# X7A15T-Decoupling.net
KiCad netlist of a schematic drawn in Altium Designer
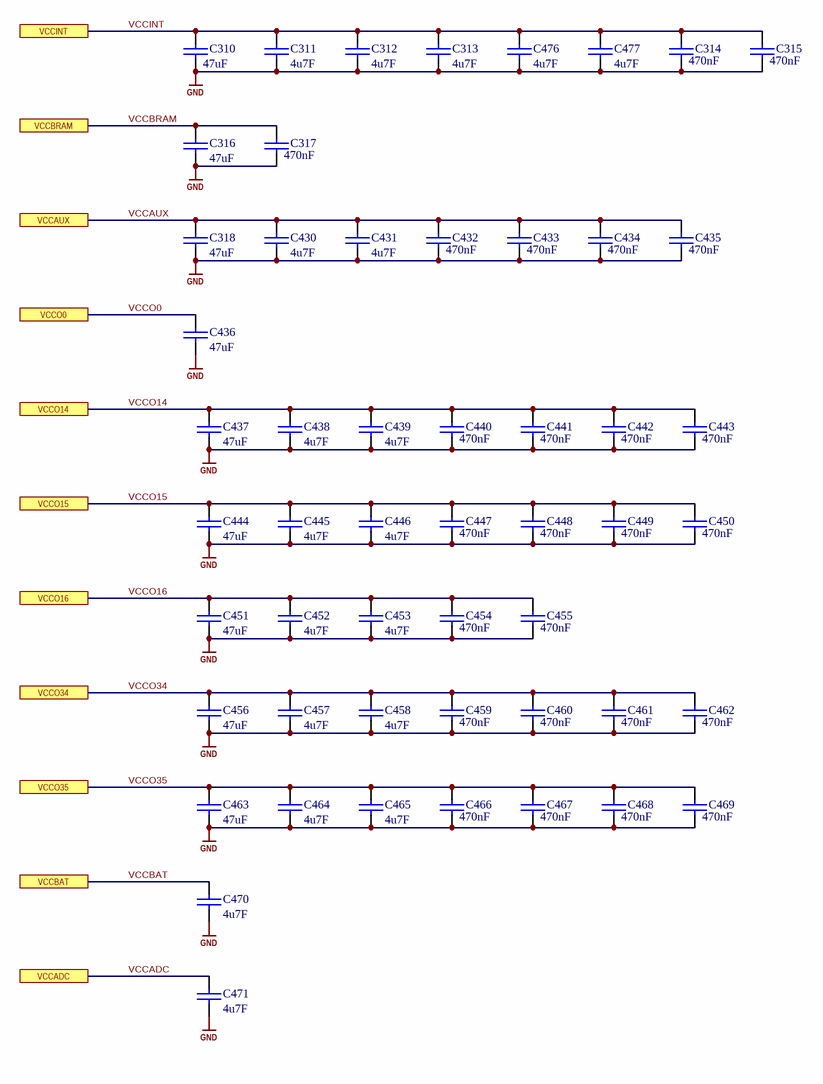
[diagram p0: X7A15T-Decoupling.SchDoc]

(export (version "E")
  (design (tool "Eeschema 10.0.6"))
  (components
    (comp (ref "C310")
      (value "47uF")
      (footprint "C1206 Reflow")
      (description "CAP CER 47UF 10V X5R 1206")
      (fields (field (name "MFR") "MURATA") (field (name "02. DISTRIBUTOR PART NUMBER") "1276-3063-6-ND"))
      (libsource (lib "SCT8-Board1") (part "CAP"))
    )
    (comp (ref "C311")
      (value "4u7F")
      (footprint "C0402 RevOne")
      (description "CAP CER 4.7UF 6.3V X5R 0402")
      (fields
        (field (name "02. DISTRIBUTOR PART NUMBER") "1276-1481-6-ND")
        (field (name "07. MANUFACTURER  PART NUMBER") "CL05A475KQ5NRNC")
      )
      (libsource (lib "SCT8-Board1") (part "CAP"))
    )
    (comp (ref "C312")
      (value "4u7F")
      (footprint "C0402 RevOne")
      (description "CAP CER 4.7UF 6.3V X5R 0402")
      (fields
        (field (name "02. DISTRIBUTOR PART NUMBER") "1276-1481-6-ND")
        (field (name "07. MANUFACTURER  PART NUMBER") "CL05A475KQ5NRNC")
      )
      (libsource (lib "SCT8-Board1") (part "CAP"))
    )
    (comp (ref "C313")
      (value "4u7F")
      (footprint "C0402 RevOne")
      (description "CAP CER 4.7UF 6.3V X5R 0402")
      (fields
        (field (name "02. DISTRIBUTOR PART NUMBER") "1276-1481-6-ND")
        (field (name "07. MANUFACTURER  PART NUMBER") "CL05A475KQ5NRNC")
      )
      (libsource (lib "SCT8-Board1") (part "CAP"))
    )
    (comp (ref "C314")
      (value "470nF")
      (footprint "C0402 RevOne")
      (description "CAP CER 0.47UF 10V X5R 0402")
      (fields
        (field (name "02. DISTRIBUTOR PART NUMBER") "1276-1173-6-ND")
        (field (name "07. MANUFACTURER  PART NUMBER") "CL05A474KP5NNNC")
      )
      (libsource (lib "SCT8-Board1") (part "CAP"))
    )
    (comp (ref "C315")
      (value "470nF")
      (footprint "C0402 RevOne")
      (description "CAP CER 0.47UF 10V X5R 0402")
      (fields
        (field (name "02. DISTRIBUTOR PART NUMBER") "1276-1173-6-ND")
        (field (name "07. MANUFACTURER  PART NUMBER") "CL05A474KP5NNNC")
      )
      (libsource (lib "SCT8-Board1") (part "CAP"))
    )
    (comp (ref "C316")
      (value "47uF")
      (footprint "C0805 Reflow")
      (description "CAP CER 47UF 10V X5R 0805")
      (fields (field (name "MFR") "MURATA") (field (name "02. DISTRIBUTOR PART NUMBER") "490-9961-6-ND"))
      (libsource (lib "SCT8-Board1") (part "CAP"))
    )
    (comp (ref "C317")
      (value "470nF")
      (footprint "C0402 RevOne")
      (description "CAP CER 0.47UF 10V X5R 0402")
      (fields
        (field (name "02. DISTRIBUTOR PART NUMBER") "1276-1173-6-ND")
        (field (name "07. MANUFACTURER  PART NUMBER") "CL05A474KP5NNNC")
      )
      (libsource (lib "SCT8-Board1") (part "CAP"))
    )
    (comp (ref "C318")
      (value "47uF")
      (footprint "C0805 Reflow")
      (description "CAP CER 47UF 10V X5R 0805")
      (fields (field (name "MFR") "MURATA") (field (name "02. DISTRIBUTOR PART NUMBER") "490-9961-6-ND"))
      (libsource (lib "SCT8-Board1") (part "CAP"))
    )
    (comp (ref "C430")
      (value "4u7F")
      (footprint "C0402 RevOne")
      (description "CAP CER 4.7UF 6.3V X5R 0402")
      (fields
        (field (name "02. DISTRIBUTOR PART NUMBER") "1276-1481-6-ND")
        (field (name "07. MANUFACTURER  PART NUMBER") "CL05A475KQ5NRNC")
      )
      (libsource (lib "SCT8-Board1") (part "CAP"))
    )
    (comp (ref "C431")
      (value "4u7F")
      (footprint "C0402 RevOne")
      (description "CAP CER 4.7UF 6.3V X5R 0402")
      (fields
        (field (name "02. DISTRIBUTOR PART NUMBER") "1276-1481-6-ND")
        (field (name "07. MANUFACTURER  PART NUMBER") "CL05A475KQ5NRNC")
      )
      (libsource (lib "SCT8-Board1") (part "CAP"))
    )
    (comp (ref "C432")
      (value "470nF")
      (footprint "C0402 RevOne")
      (description "CAP CER 0.47UF 10V X5R 0402")
      (fields
        (field (name "02. DISTRIBUTOR PART NUMBER") "1276-1173-6-ND")
        (field (name "07. MANUFACTURER  PART NUMBER") "CL05A474KP5NNNC")
      )
      (libsource (lib "SCT8-Board1") (part "CAP"))
    )
    (comp (ref "C433")
      (value "470nF")
      (footprint "C0402 RevOne")
      (description "CAP CER 0.47UF 10V X5R 0402")
      (fields
        (field (name "02. DISTRIBUTOR PART NUMBER") "1276-1173-6-ND")
        (field (name "07. MANUFACTURER  PART NUMBER") "CL05A474KP5NNNC")
      )
      (libsource (lib "SCT8-Board1") (part "CAP"))
    )
    (comp (ref "C434")
      (value "470nF")
      (footprint "C0402 RevOne")
      (description "CAP CER 0.47UF 10V X5R 0402")
      (fields
        (field (name "02. DISTRIBUTOR PART NUMBER") "1276-1173-6-ND")
        (field (name "07. MANUFACTURER  PART NUMBER") "CL05A474KP5NNNC")
      )
      (libsource (lib "SCT8-Board1") (part "CAP"))
    )
    (comp (ref "C435")
      (value "470nF")
      (footprint "C0402 RevOne")
      (description "CAP CER 0.47UF 10V X5R 0402")
      (fields
        (field (name "02. DISTRIBUTOR PART NUMBER") "1276-1173-6-ND")
        (field (name "07. MANUFACTURER  PART NUMBER") "CL05A474KP5NNNC")
      )
      (libsource (lib "SCT8-Board1") (part "CAP"))
    )
    (comp (ref "C436")
      (value "47uF")
      (footprint "C0805 Reflow")
      (description "CAP CER 47UF 10V X5R 0805")
      (fields (field (name "MFR") "MURATA") (field (name "02. DISTRIBUTOR PART NUMBER") "490-9961-6-ND"))
      (libsource (lib "SCT8-Board1") (part "CAP"))
    )
    (comp (ref "C437")
      (value "47uF")
      (footprint "C0805 Reflow")
      (description "CAP CER 47UF 10V X5R 0805")
      (fields (field (name "MFR") "MURATA") (field (name "02. DISTRIBUTOR PART NUMBER") "490-9961-6-ND"))
      (libsource (lib "SCT8-Board1") (part "CAP"))
    )
    (comp (ref "C438")
      (value "4u7F")
      (footprint "C0402 RevOne")
      (description "CAP CER 4.7UF 6.3V X5R 0402")
      (fields
        (field (name "02. DISTRIBUTOR PART NUMBER") "1276-1481-6-ND")
        (field (name "07. MANUFACTURER  PART NUMBER") "CL05A475KQ5NRNC")
      )
      (libsource (lib "SCT8-Board1") (part "CAP"))
    )
    (comp (ref "C439")
      (value "4u7F")
      (footprint "C0402 RevOne")
      (description "CAP CER 4.7UF 6.3V X5R 0402")
      (fields
        (field (name "02. DISTRIBUTOR PART NUMBER") "1276-1481-6-ND")
        (field (name "07. MANUFACTURER  PART NUMBER") "CL05A475KQ5NRNC")
      )
      (libsource (lib "SCT8-Board1") (part "CAP"))
    )
    (comp (ref "C440")
      (value "470nF")
      (footprint "C0402 RevOne")
      (description "CAP CER 0.47UF 10V X5R 0402")
      (fields
        (field (name "02. DISTRIBUTOR PART NUMBER") "1276-1173-6-ND")
        (field (name "07. MANUFACTURER  PART NUMBER") "CL05A474KP5NNNC")
      )
      (libsource (lib "SCT8-Board1") (part "CAP"))
    )
    (comp (ref "C441")
      (value "470nF")
      (footprint "C0402 RevOne")
      (description "CAP CER 0.47UF 10V X5R 0402")
      (fields
        (field (name "02. DISTRIBUTOR PART NUMBER") "1276-1173-6-ND")
        (field (name "07. MANUFACTURER  PART NUMBER") "CL05A474KP5NNNC")
      )
      (libsource (lib "SCT8-Board1") (part "CAP"))
    )
    (comp (ref "C442")
      (value "470nF")
      (footprint "C0402 RevOne")
      (description "CAP CER 0.47UF 10V X5R 0402")
      (fields
        (field (name "02. DISTRIBUTOR PART NUMBER") "1276-1173-6-ND")
        (field (name "07. MANUFACTURER  PART NUMBER") "CL05A474KP5NNNC")
      )
      (libsource (lib "SCT8-Board1") (part "CAP"))
    )
    (comp (ref "C443")
      (value "470nF")
      (footprint "C0402 RevOne")
      (description "CAP CER 0.47UF 10V X5R 0402")
      (fields
        (field (name "02. DISTRIBUTOR PART NUMBER") "1276-1173-6-ND")
        (field (name "07. MANUFACTURER  PART NUMBER") "CL05A474KP5NNNC")
      )
      (libsource (lib "SCT8-Board1") (part "CAP"))
    )
    (comp (ref "C444")
      (value "47uF")
      (footprint "C0805 Reflow")
      (description "CAP CER 47UF 10V X5R 0805")
      (fields (field (name "MFR") "MURATA") (field (name "02. DISTRIBUTOR PART NUMBER") "490-9961-6-ND"))
      (libsource (lib "SCT8-Board1") (part "CAP"))
    )
    (comp (ref "C445")
      (value "4u7F")
      (footprint "C0402 RevOne")
      (description "CAP CER 4.7UF 6.3V X5R 0402")
      (fields
        (field (name "02. DISTRIBUTOR PART NUMBER") "1276-1481-6-ND")
        (field (name "07. MANUFACTURER  PART NUMBER") "CL05A475KQ5NRNC")
      )
      (libsource (lib "SCT8-Board1") (part "CAP"))
    )
    (comp (ref "C446")
      (value "4u7F")
      (footprint "C0402 RevOne")
      (description "CAP CER 4.7UF 6.3V X5R 0402")
      (fields
        (field (name "02. DISTRIBUTOR PART NUMBER") "1276-1481-6-ND")
        (field (name "07. MANUFACTURER  PART NUMBER") "CL05A475KQ5NRNC")
      )
      (libsource (lib "SCT8-Board1") (part "CAP"))
    )
    (comp (ref "C447")
      (value "470nF")
      (footprint "C0402 RevOne")
      (description "CAP CER 0.47UF 10V X5R 0402")
      (fields
        (field (name "02. DISTRIBUTOR PART NUMBER") "1276-1173-6-ND")
        (field (name "07. MANUFACTURER  PART NUMBER") "CL05A474KP5NNNC")
      )
      (libsource (lib "SCT8-Board1") (part "CAP"))
    )
    (comp (ref "C448")
      (value "470nF")
      (footprint "C0402 RevOne")
      (description "CAP CER 0.47UF 10V X5R 0402")
      (fields
        (field (name "02. DISTRIBUTOR PART NUMBER") "1276-1173-6-ND")
        (field (name "07. MANUFACTURER  PART NUMBER") "CL05A474KP5NNNC")
      )
      (libsource (lib "SCT8-Board1") (part "CAP"))
    )
    (comp (ref "C449")
      (value "470nF")
      (footprint "C0402 RevOne")
      (description "CAP CER 0.47UF 10V X5R 0402")
      (fields
        (field (name "02. DISTRIBUTOR PART NUMBER") "1276-1173-6-ND")
        (field (name "07. MANUFACTURER  PART NUMBER") "CL05A474KP5NNNC")
      )
      (libsource (lib "SCT8-Board1") (part "CAP"))
    )
    (comp (ref "C450")
      (value "470nF")
      (footprint "C0402 RevOne")
      (description "CAP CER 0.47UF 10V X5R 0402")
      (fields
        (field (name "02. DISTRIBUTOR PART NUMBER") "1276-1173-6-ND")
        (field (name "07. MANUFACTURER  PART NUMBER") "CL05A474KP5NNNC")
      )
      (libsource (lib "SCT8-Board1") (part "CAP"))
    )
    (comp (ref "C451")
      (value "47uF")
      (footprint "C0805 Reflow")
      (description "CAP CER 47UF 10V X5R 0805")
      (fields (field (name "MFR") "MURATA") (field (name "02. DISTRIBUTOR PART NUMBER") "490-9961-6-ND"))
      (libsource (lib "SCT8-Board1") (part "CAP"))
    )
    (comp (ref "C452")
      (value "4u7F")
      (footprint "C0402 RevOne")
      (description "CAP CER 4.7UF 6.3V X5R 0402")
      (fields
        (field (name "02. DISTRIBUTOR PART NUMBER") "1276-1481-6-ND")
        (field (name "07. MANUFACTURER  PART NUMBER") "CL05A475KQ5NRNC")
      )
      (libsource (lib "SCT8-Board1") (part "CAP"))
    )
    (comp (ref "C453")
      (value "4u7F")
      (footprint "C0402 RevOne")
      (description "CAP CER 4.7UF 6.3V X5R 0402")
      (fields
        (field (name "02. DISTRIBUTOR PART NUMBER") "1276-1481-6-ND")
        (field (name "07. MANUFACTURER  PART NUMBER") "CL05A475KQ5NRNC")
      )
      (libsource (lib "SCT8-Board1") (part "CAP"))
    )
    (comp (ref "C454")
      (value "470nF")
      (footprint "C0402 RevOne")
      (description "CAP CER 0.47UF 10V X5R 0402")
      (fields
        (field (name "02. DISTRIBUTOR PART NUMBER") "1276-1173-6-ND")
        (field (name "07. MANUFACTURER  PART NUMBER") "CL05A474KP5NNNC")
      )
      (libsource (lib "SCT8-Board1") (part "CAP"))
    )
    (comp (ref "C455")
      (value "470nF")
      (footprint "C0402 RevOne")
      (description "CAP CER 0.47UF 10V X5R 0402")
      (fields
        (field (name "02. DISTRIBUTOR PART NUMBER") "1276-1173-6-ND")
        (field (name "07. MANUFACTURER  PART NUMBER") "CL05A474KP5NNNC")
      )
      (libsource (lib "SCT8-Board1") (part "CAP"))
    )
    (comp (ref "C456")
      (value "47uF")
      (footprint "C0805 Reflow")
      (description "CAP CER 47UF 10V X5R 0805")
      (fields (field (name "MFR") "MURATA") (field (name "02. DISTRIBUTOR PART NUMBER") "490-9961-6-ND"))
      (libsource (lib "SCT8-Board1") (part "CAP"))
    )
    (comp (ref "C457")
      (value "4u7F")
      (footprint "C0402 RevOne")
      (description "CAP CER 4.7UF 6.3V X5R 0402")
      (fields
        (field (name "02. DISTRIBUTOR PART NUMBER") "1276-1481-6-ND")
        (field (name "07. MANUFACTURER  PART NUMBER") "CL05A475KQ5NRNC")
      )
      (libsource (lib "SCT8-Board1") (part "CAP"))
    )
    (comp (ref "C458")
      (value "4u7F")
      (footprint "C0402 RevOne")
      (description "CAP CER 4.7UF 6.3V X5R 0402")
      (fields
        (field (name "02. DISTRIBUTOR PART NUMBER") "1276-1481-6-ND")
        (field (name "07. MANUFACTURER  PART NUMBER") "CL05A475KQ5NRNC")
      )
      (libsource (lib "SCT8-Board1") (part "CAP"))
    )
    (comp (ref "C459")
      (value "470nF")
      (footprint "C0402 RevOne")
      (description "CAP CER 0.47UF 10V X5R 0402")
      (fields
        (field (name "02. DISTRIBUTOR PART NUMBER") "1276-1173-6-ND")
        (field (name "07. MANUFACTURER  PART NUMBER") "CL05A474KP5NNNC")
      )
      (libsource (lib "SCT8-Board1") (part "CAP"))
    )
    (comp (ref "C460")
      (value "470nF")
      (footprint "C0402 RevOne")
      (description "CAP CER 0.47UF 10V X5R 0402")
      (fields
        (field (name "02. DISTRIBUTOR PART NUMBER") "1276-1173-6-ND")
        (field (name "07. MANUFACTURER  PART NUMBER") "CL05A474KP5NNNC")
      )
      (libsource (lib "SCT8-Board1") (part "CAP"))
    )
    (comp (ref "C461")
      (value "470nF")
      (footprint "C0402 RevOne")
      (description "CAP CER 0.47UF 10V X5R 0402")
      (fields
        (field (name "02. DISTRIBUTOR PART NUMBER") "1276-1173-6-ND")
        (field (name "07. MANUFACTURER  PART NUMBER") "CL05A474KP5NNNC")
      )
      (libsource (lib "SCT8-Board1") (part "CAP"))
    )
    (comp (ref "C462")
      (value "470nF")
      (footprint "C0402 RevOne")
      (description "CAP CER 0.47UF 10V X5R 0402")
      (fields
        (field (name "02. DISTRIBUTOR PART NUMBER") "1276-1173-6-ND")
        (field (name "07. MANUFACTURER  PART NUMBER") "CL05A474KP5NNNC")
      )
      (libsource (lib "SCT8-Board1") (part "CAP"))
    )
    (comp (ref "C463")
      (value "47uF")
      (footprint "C0805 Reflow")
      (description "CAP CER 47UF 10V X5R 0805")
      (fields (field (name "MFR") "MURATA") (field (name "02. DISTRIBUTOR PART NUMBER") "490-9961-6-ND"))
      (libsource (lib "SCT8-Board1") (part "CAP"))
    )
    (comp (ref "C464")
      (value "4u7F")
      (footprint "C0402 RevOne")
      (description "CAP CER 4.7UF 6.3V X5R 0402")
      (fields
        (field (name "02. DISTRIBUTOR PART NUMBER") "1276-1481-6-ND")
        (field (name "07. MANUFACTURER  PART NUMBER") "CL05A475KQ5NRNC")
      )
      (libsource (lib "SCT8-Board1") (part "CAP"))
    )
    (comp (ref "C465")
      (value "4u7F")
      (footprint "C0402 RevOne")
      (description "CAP CER 4.7UF 6.3V X5R 0402")
      (fields
        (field (name "02. DISTRIBUTOR PART NUMBER") "1276-1481-6-ND")
        (field (name "07. MANUFACTURER  PART NUMBER") "CL05A475KQ5NRNC")
      )
      (libsource (lib "SCT8-Board1") (part "CAP"))
    )
    (comp (ref "C466")
      (value "470nF")
      (footprint "C0402 RevOne")
      (description "CAP CER 0.47UF 10V X5R 0402")
      (fields
        (field (name "02. DISTRIBUTOR PART NUMBER") "1276-1173-6-ND")
        (field (name "07. MANUFACTURER  PART NUMBER") "CL05A474KP5NNNC")
      )
      (libsource (lib "SCT8-Board1") (part "CAP"))
    )
    (comp (ref "C467")
      (value "470nF")
      (footprint "C0402 RevOne")
      (description "CAP CER 0.47UF 10V X5R 0402")
      (fields
        (field (name "02. DISTRIBUTOR PART NUMBER") "1276-1173-6-ND")
        (field (name "07. MANUFACTURER  PART NUMBER") "CL05A474KP5NNNC")
      )
      (libsource (lib "SCT8-Board1") (part "CAP"))
    )
    (comp (ref "C468")
      (value "470nF")
      (footprint "C0402 RevOne")
      (description "CAP CER 0.47UF 10V X5R 0402")
      (fields
        (field (name "02. DISTRIBUTOR PART NUMBER") "1276-1173-6-ND")
        (field (name "07. MANUFACTURER  PART NUMBER") "CL05A474KP5NNNC")
      )
      (libsource (lib "SCT8-Board1") (part "CAP"))
    )
    (comp (ref "C469")
      (value "470nF")
      (footprint "C0402 RevOne")
      (description "CAP CER 0.47UF 10V X5R 0402")
      (fields
        (field (name "02. DISTRIBUTOR PART NUMBER") "1276-1173-6-ND")
        (field (name "07. MANUFACTURER  PART NUMBER") "CL05A474KP5NNNC")
      )
      (libsource (lib "SCT8-Board1") (part "CAP"))
    )
    (comp (ref "C470")
      (value "4u7F")
      (footprint "C0402 RevOne")
      (description "CAP CER 4.7UF 6.3V X5R 0402")
      (fields
        (field (name "02. DISTRIBUTOR PART NUMBER") "1276-1481-6-ND")
        (field (name "07. MANUFACTURER  PART NUMBER") "CL05A475KQ5NRNC")
      )
      (libsource (lib "SCT8-Board1") (part "CAP"))
    )
    (comp (ref "C471")
      (value "4u7F")
      (footprint "C0402 RevOne")
      (description "CAP CER 4.7UF 6.3V X5R 0402")
      (fields
        (field (name "02. DISTRIBUTOR PART NUMBER") "1276-1481-6-ND")
        (field (name "07. MANUFACTURER  PART NUMBER") "CL05A475KQ5NRNC")
      )
      (libsource (lib "SCT8-Board1") (part "CAP"))
    )
    (comp (ref "C476")
      (value "4u7F")
      (footprint "C0402 RevOne")
      (description "CAP CER 4.7UF 6.3V X5R 0402")
      (fields
        (field (name "02. DISTRIBUTOR PART NUMBER") "1276-1481-6-ND")
        (field (name "07. MANUFACTURER  PART NUMBER") "CL05A475KQ5NRNC")
      )
      (libsource (lib "SCT8-Board1") (part "CAP"))
    )
    (comp (ref "C477")
      (value "4u7F")
      (footprint "C0402 RevOne")
      (description "CAP CER 4.7UF 6.3V X5R 0402")
      (fields
        (field (name "02. DISTRIBUTOR PART NUMBER") "1276-1481-6-ND")
        (field (name "07. MANUFACTURER  PART NUMBER") "CL05A475KQ5NRNC")
      )
      (libsource (lib "SCT8-Board1") (part "CAP"))
    )
  )
  (nets
    (net (code "1") (name "/VCCADC") (class "Default")
      (node (ref "C471") (pin "1") (pinfunction "1_1") (pintype "passive"))
    )
    (net (code "2") (name "/VCCAUX") (class "Default")
      (node (ref "C318") (pin "1") (pinfunction "1_1") (pintype "passive"))
      (node (ref "C430") (pin "1") (pinfunction "1_1") (pintype "passive"))
      (node (ref "C431") (pin "1") (pinfunction "1_1") (pintype "passive"))
      (node (ref "C432") (pin "1") (pinfunction "1_1") (pintype "passive"))
      (node (ref "C433") (pin "1") (pinfunction "1_1") (pintype "passive"))
      (node (ref "C434") (pin "1") (pinfunction "1_1") (pintype "passive"))
      (node (ref "C435") (pin "1") (pinfunction "1_1") (pintype "passive"))
    )
    (net (code "3") (name "/VCCBAT") (class "Default")
      (node (ref "C470") (pin "1") (pinfunction "1_1") (pintype "passive"))
    )
    (net (code "4") (name "/VCCBRAM") (class "Default")
      (node (ref "C316") (pin "1") (pinfunction "1_1") (pintype "passive"))
      (node (ref "C317") (pin "1") (pinfunction "1_1") (pintype "passive"))
    )
    (net (code "5") (name "/VCCINT") (class "Default")
      (node (ref "C310") (pin "1") (pinfunction "1_1") (pintype "passive"))
      (node (ref "C311") (pin "1") (pinfunction "1_1") (pintype "passive"))
      (node (ref "C312") (pin "1") (pinfunction "1_1") (pintype "passive"))
      (node (ref "C313") (pin "1") (pinfunction "1_1") (pintype "passive"))
      (node (ref "C314") (pin "1") (pinfunction "1_1") (pintype "passive"))
      (node (ref "C315") (pin "1") (pinfunction "1_1") (pintype "passive"))
      (node (ref "C476") (pin "1") (pinfunction "1_1") (pintype "passive"))
      (node (ref "C477") (pin "1") (pinfunction "1_1") (pintype "passive"))
    )
    (net (code "6") (name "/VCCO0") (class "Default")
      (node (ref "C436") (pin "1") (pinfunction "1_1") (pintype "passive"))
    )
    (net (code "7") (name "/VCCO14") (class "Default")
      (node (ref "C437") (pin "1") (pinfunction "1_1") (pintype "passive"))
      (node (ref "C438") (pin "1") (pinfunction "1_1") (pintype "passive"))
      (node (ref "C439") (pin "1") (pinfunction "1_1") (pintype "passive"))
      (node (ref "C440") (pin "1") (pinfunction "1_1") (pintype "passive"))
      (node (ref "C441") (pin "1") (pinfunction "1_1") (pintype "passive"))
      (node (ref "C442") (pin "1") (pinfunction "1_1") (pintype "passive"))
      (node (ref "C443") (pin "1") (pinfunction "1_1") (pintype "passive"))
    )
    (net (code "8") (name "/VCCO15") (class "Default")
      (node (ref "C444") (pin "1") (pinfunction "1_1") (pintype "passive"))
      (node (ref "C445") (pin "1") (pinfunction "1_1") (pintype "passive"))
      (node (ref "C446") (pin "1") (pinfunction "1_1") (pintype "passive"))
      (node (ref "C447") (pin "1") (pinfunction "1_1") (pintype "passive"))
      (node (ref "C448") (pin "1") (pinfunction "1_1") (pintype "passive"))
      (node (ref "C449") (pin "1") (pinfunction "1_1") (pintype "passive"))
      (node (ref "C450") (pin "1") (pinfunction "1_1") (pintype "passive"))
    )
    (net (code "9") (name "/VCCO16") (class "Default")
      (node (ref "C451") (pin "1") (pinfunction "1_1") (pintype "passive"))
      (node (ref "C452") (pin "1") (pinfunction "1_1") (pintype "passive"))
      (node (ref "C453") (pin "1") (pinfunction "1_1") (pintype "passive"))
      (node (ref "C454") (pin "1") (pinfunction "1_1") (pintype "passive"))
      (node (ref "C455") (pin "1") (pinfunction "1_1") (pintype "passive"))
    )
    (net (code "10") (name "/VCCO34") (class "Default")
      (node (ref "C456") (pin "1") (pinfunction "1_1") (pintype "passive"))
      (node (ref "C457") (pin "1") (pinfunction "1_1") (pintype "passive"))
      (node (ref "C458") (pin "1") (pinfunction "1_1") (pintype "passive"))
      (node (ref "C459") (pin "1") (pinfunction "1_1") (pintype "passive"))
      (node (ref "C460") (pin "1") (pinfunction "1_1") (pintype "passive"))
      (node (ref "C461") (pin "1") (pinfunction "1_1") (pintype "passive"))
      (node (ref "C462") (pin "1") (pinfunction "1_1") (pintype "passive"))
    )
    (net (code "11") (name "/VCCO35") (class "Default")
      (node (ref "C463") (pin "1") (pinfunction "1_1") (pintype "passive"))
      (node (ref "C464") (pin "1") (pinfunction "1_1") (pintype "passive"))
      (node (ref "C465") (pin "1") (pinfunction "1_1") (pintype "passive"))
      (node (ref "C466") (pin "1") (pinfunction "1_1") (pintype "passive"))
      (node (ref "C467") (pin "1") (pinfunction "1_1") (pintype "passive"))
      (node (ref "C468") (pin "1") (pinfunction "1_1") (pintype "passive"))
      (node (ref "C469") (pin "1") (pinfunction "1_1") (pintype "passive"))
    )
    (net (code "12") (name "GND") (class "Default")
      (node (ref "C310") (pin "2") (pinfunction "2_2") (pintype "passive"))
      (node (ref "C311") (pin "2") (pinfunction "2_2") (pintype "passive"))
      (node (ref "C312") (pin "2") (pinfunction "2_2") (pintype "passive"))
      (node (ref "C313") (pin "2") (pinfunction "2_2") (pintype "passive"))
      (node (ref "C314") (pin "2") (pinfunction "2_2") (pintype "passive"))
      (node (ref "C315") (pin "2") (pinfunction "2_2") (pintype "passive"))
      (node (ref "C316") (pin "2") (pinfunction "2_2") (pintype "passive"))
      (node (ref "C317") (pin "2") (pinfunction "2_2") (pintype "passive"))
      (node (ref "C318") (pin "2") (pinfunction "2_2") (pintype "passive"))
      (node (ref "C430") (pin "2") (pinfunction "2_2") (pintype "passive"))
      (node (ref "C431") (pin "2") (pinfunction "2_2") (pintype "passive"))
      (node (ref "C432") (pin "2") (pinfunction "2_2") (pintype "passive"))
      (node (ref "C433") (pin "2") (pinfunction "2_2") (pintype "passive"))
      (node (ref "C434") (pin "2") (pinfunction "2_2") (pintype "passive"))
      (node (ref "C435") (pin "2") (pinfunction "2_2") (pintype "passive"))
      (node (ref "C436") (pin "2") (pinfunction "2_2") (pintype "passive"))
      (node (ref "C437") (pin "2") (pinfunction "2_2") (pintype "passive"))
      (node (ref "C438") (pin "2") (pinfunction "2_2") (pintype "passive"))
      (node (ref "C439") (pin "2") (pinfunction "2_2") (pintype "passive"))
      (node (ref "C440") (pin "2") (pinfunction "2_2") (pintype "passive"))
      (node (ref "C441") (pin "2") (pinfunction "2_2") (pintype "passive"))
      (node (ref "C442") (pin "2") (pinfunction "2_2") (pintype "passive"))
      (node (ref "C443") (pin "2") (pinfunction "2_2") (pintype "passive"))
      (node (ref "C444") (pin "2") (pinfunction "2_2") (pintype "passive"))
      (node (ref "C445") (pin "2") (pinfunction "2_2") (pintype "passive"))
      (node (ref "C446") (pin "2") (pinfunction "2_2") (pintype "passive"))
      (node (ref "C447") (pin "2") (pinfunction "2_2") (pintype "passive"))
      (node (ref "C448") (pin "2") (pinfunction "2_2") (pintype "passive"))
      (node (ref "C449") (pin "2") (pinfunction "2_2") (pintype "passive"))
      (node (ref "C450") (pin "2") (pinfunction "2_2") (pintype "passive"))
      (node (ref "C451") (pin "2") (pinfunction "2_2") (pintype "passive"))
      (node (ref "C452") (pin "2") (pinfunction "2_2") (pintype "passive"))
      (node (ref "C453") (pin "2") (pinfunction "2_2") (pintype "passive"))
      (node (ref "C454") (pin "2") (pinfunction "2_2") (pintype "passive"))
      (node (ref "C455") (pin "2") (pinfunction "2_2") (pintype "passive"))
      (node (ref "C456") (pin "2") (pinfunction "2_2") (pintype "passive"))
      (node (ref "C457") (pin "2") (pinfunction "2_2") (pintype "passive"))
      (node (ref "C458") (pin "2") (pinfunction "2_2") (pintype "passive"))
      (node (ref "C459") (pin "2") (pinfunction "2_2") (pintype "passive"))
      (node (ref "C460") (pin "2") (pinfunction "2_2") (pintype "passive"))
      (node (ref "C461") (pin "2") (pinfunction "2_2") (pintype "passive"))
      (node (ref "C462") (pin "2") (pinfunction "2_2") (pintype "passive"))
      (node (ref "C463") (pin "2") (pinfunction "2_2") (pintype "passive"))
      (node (ref "C464") (pin "2") (pinfunction "2_2") (pintype "passive"))
      (node (ref "C465") (pin "2") (pinfunction "2_2") (pintype "passive"))
      (node (ref "C466") (pin "2") (pinfunction "2_2") (pintype "passive"))
      (node (ref "C467") (pin "2") (pinfunction "2_2") (pintype "passive"))
      (node (ref "C468") (pin "2") (pinfunction "2_2") (pintype "passive"))
      (node (ref "C469") (pin "2") (pinfunction "2_2") (pintype "passive"))
      (node (ref "C470") (pin "2") (pinfunction "2_2") (pintype "passive"))
      (node (ref "C471") (pin "2") (pinfunction "2_2") (pintype "passive"))
      (node (ref "C476") (pin "2") (pinfunction "2_2") (pintype "passive"))
      (node (ref "C477") (pin "2") (pinfunction "2_2") (pintype "passive"))
    )
  )
)
